# PLD_Local-Supply.net
KiCad netlist of a schematic drawn in Altium Designer
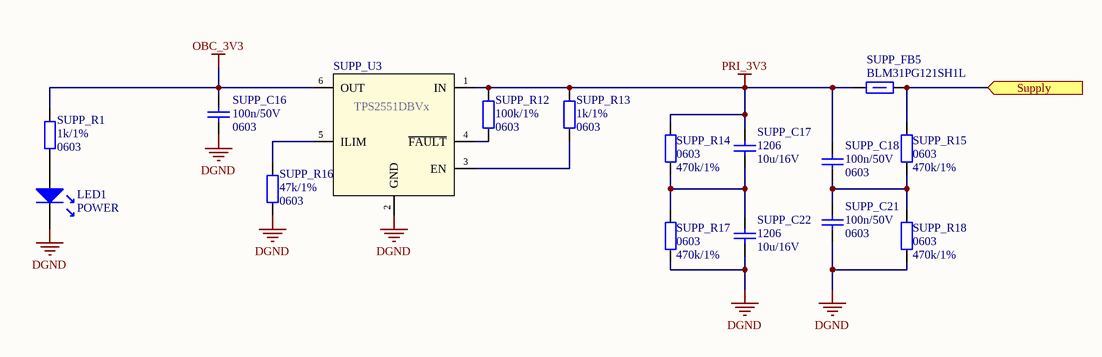
[diagram p0: PLD_Local-Supply.SchDoc]

(export (version "E")
  (design (tool "Eeschema 10.0.6"))
  (components
    (comp (ref "LED1")
      (value "POWER")
      (footprint "SMD_LED_1206")
      (description "LED diode, SMD1206 package.")
      (libsource (lib "diodes") (part "LED-1206_RED"))
    )
    (comp (ref "SUPP_C16")
      (value "100n/50V")
      (footprint "SMD_Capacitor_0603")
      (description "Ceramic Cap Kemet COTS 100n/50V X7R 0603")
      (fields
        (field (name "MANUFACTURER") "Kemet")
        (field (name "MANUFACTURERPARTNUMBER") "C0603T104K5RALTU")
        (field (name "PACKAGE") "0603")
      )
      (libsource (lib "capacitors") (part "Cer_C0603T104K5RALTU"))
    )
    (comp (ref "SUPP_C17")
      (value "10u/16V")
      (footprint "SMD_Capacitor_1206")
      (description "Ceramic Cap Kemet COTS 10u/16V X7R 1206")
      (fields
        (field (name "MANUFACTURERPARTNUMBER") "C1206T106K4RACTU")
        (field (name "MANUFACTURER") "Kemet")
        (field (name "PACKGE") "1206")
      )
      (libsource (lib "capacitors") (part "Cer_C1206T106K4RACTU"))
    )
    (comp (ref "SUPP_C18")
      (value "100n/50V")
      (footprint "SMD_Capacitor_0603")
      (description "Ceramic Cap Kemet COTS 100n/50V X7R 0603")
      (fields
        (field (name "MANUFACTURER") "Kemet")
        (field (name "MANUFACTURERPARTNUMBER") "C0603T104K5RALTU")
        (field (name "PACKAGE") "0603")
      )
      (libsource (lib "capacitors") (part "Cer_C0603T104K5RALTU"))
    )
    (comp (ref "SUPP_C21")
      (value "100n/50V")
      (footprint "SMD_Capacitor_0603")
      (description "Ceramic Cap Kemet COTS 100n/50V X7R 0603")
      (fields
        (field (name "MANUFACTURER") "Kemet")
        (field (name "MANUFACTURERPARTNUMBER") "C0603T104K5RALTU")
        (field (name "PACKAGE") "0603")
      )
      (libsource (lib "capacitors") (part "Cer_C0603T104K5RALTU"))
    )
    (comp (ref "SUPP_C22")
      (value "10u/16V")
      (footprint "SMD_Capacitor_1206")
      (description "Ceramic Cap Kemet COTS 10u/16V X7R 1206")
      (fields
        (field (name "MANUFACTURERPARTNUMBER") "C1206T106K4RACTU")
        (field (name "MANUFACTURER") "Kemet")
        (field (name "PACKGE") "1206")
      )
      (libsource (lib "capacitors") (part "Cer_C1206T106K4RACTU"))
    )
    (comp (ref "SUPP_FB5")
      (value "120R/100MHz")
      (footprint "SMD_FerriteBead_1206")
      (description "Ferrite bead, 1206, 0.02HM, 3.5A.")
      (fields (field (name "MANUFACTURER") "Murata") (field (name "MANUFACTURERPARTNUMBER") "BLM31PG121SH1L"))
      (libsource (lib "inductors") (part "BLM31PG121SH1L"))
    )
    (comp (ref "SUPP_R1")
      (value "1k/1%")
      (footprint "SMD_Resistor_0603")
      (description "1k/1% Vishay CRCW 0603 Resistor. 100mW, 100ppm, 75V.")
      (fields
        (field (name "MANUFACTURER") "Vishay")
        (field (name "MANUFACTURERPARTNUMBER") "CRCW06031K00FKxxxx")
        (field (name "PACKAGE") "0603")
      )
      (libsource (lib "resistors") (part "CRCW06031K00FKxxxx"))
    )
    (comp (ref "SUPP_R12")
      (value "100k/1%")
      (footprint "SMD_Resistor_0603")
      (description "100k/1% Vishay CRCW 0603 Resistor. 100mW, 100ppm, 75V.")
      (fields
        (field (name "MANUFACTURER") "Vishay")
        (field (name "MANUFACTURERPARTNUMBER") "CRCW0603100KFKxxxx")
        (field (name "PACKAGE") "0603")
      )
      (libsource (lib "resistors") (part "CRCW0603100KFKxxxx"))
    )
    (comp (ref "SUPP_R13")
      (value "1k/1%")
      (footprint "SMD_Resistor_0603")
      (description "1k/1% Vishay CRCW 0603 Resistor. 100mW, 100ppm, 75V.")
      (fields
        (field (name "MANUFACTURER") "Vishay")
        (field (name "MANUFACTURERPARTNUMBER") "CRCW06031K00FKxxxx")
        (field (name "PACKAGE") "0603")
      )
      (libsource (lib "resistors") (part "CRCW06031K00FKxxxx"))
    )
    (comp (ref "SUPP_R14")
      (value "470k/1%")
      (footprint "SMD_Resistor_0603")
      (description "470k/1% Vishay CRCW 0603 Resistor. 100mW, 100ppm, 75V.")
      (fields
        (field (name "MANUFACTURER") "Vishay")
        (field (name "MANUFACTURERPARTNUMBER") "CRCW0603470KFKxxxx")
        (field (name "PACKAGE") "0603")
      )
      (libsource (lib "resistors") (part "CRCW0603470KFKxxxx"))
    )
    (comp (ref "SUPP_R15")
      (value "470k/1%")
      (footprint "SMD_Resistor_0603")
      (description "470k/1% Vishay CRCW 0603 Resistor. 100mW, 100ppm, 75V.")
      (fields
        (field (name "MANUFACTURER") "Vishay")
        (field (name "MANUFACTURERPARTNUMBER") "CRCW0603470KFKxxxx")
        (field (name "PACKAGE") "0603")
      )
      (libsource (lib "") (part "CRCW0603470KFKxxxx_1"))
    )
    (comp (ref "SUPP_R16")
      (value "47k/1%")
      (footprint "SMD_Resistor_0603")
      (description "47k/1% Vishay CRCW 0603 Resistor. 100mW, 100ppm, 75V.")
      (fields
        (field (name "MANUFACTURER") "Vishay")
        (field (name "MANUFACTURERPARTNUMBER") "CRCW060347K0FKxxxx")
        (field (name "PACKAGE") "0603")
      )
      (libsource (lib "resistors") (part "CRCW060347K0FKxxxx"))
    )
    (comp (ref "SUPP_R17")
      (value "470k/1%")
      (footprint "SMD_Resistor_0603")
      (description "470k/1% Vishay CRCW 0603 Resistor. 100mW, 100ppm, 75V.")
      (fields
        (field (name "MANUFACTURER") "Vishay")
        (field (name "MANUFACTURERPARTNUMBER") "CRCW0603470KFKxxxx")
        (field (name "PACKAGE") "0603")
      )
      (libsource (lib "resistors") (part "CRCW0603470KFKxxxx"))
    )
    (comp (ref "SUPP_R18")
      (value "470k/1%")
      (footprint "SMD_Resistor_0603")
      (description "470k/1% Vishay CRCW 0603 Resistor. 100mW, 100ppm, 75V.")
      (fields
        (field (name "MANUFACTURER") "Vishay")
        (field (name "MANUFACTURERPARTNUMBER") "CRCW0603470KFKxxxx")
        (field (name "PACKAGE") "0603")
      )
      (libsource (lib "") (part "CRCW0603470KFKxxxx_1"))
    )
    (comp (ref "SUPP_U3")
      (value "TPS2551DBVx")
      (footprint "SOT23-6")
      (description "Adjustable Current-Limited Power-Distribution Switch.")
      (fields (field (name "MANUFACTURER") "Texas Instruments"))
      (libsource (lib "microcircuits") (part "TPS2551DBVx"))
    )
  )
  (nets
    (net (code "1") (name "/Supply") (class "Default")
      (node (ref "SUPP_FB5") (pin "1") (pinfunction "1_1") (pintype "passive"))
      (node (ref "SUPP_R15") (pin "1") (pinfunction "1_1") (pintype "passive"))
    )
    (net (code "2") (name "DGND") (class "Default")
      (node (ref "LED1") (pin "K") (pinfunction "K_K") (pintype "passive"))
      (node (ref "SUPP_C16") (pin "1") (pinfunction "1_1") (pintype "passive"))
      (node (ref "SUPP_C21") (pin "2") (pinfunction "2_2") (pintype "passive"))
      (node (ref "SUPP_C22") (pin "2") (pinfunction "2_2") (pintype "passive"))
      (node (ref "SUPP_R16") (pin "2") (pinfunction "2_2") (pintype "passive"))
      (node (ref "SUPP_R17") (pin "2") (pinfunction "2_2") (pintype "passive"))
      (node (ref "SUPP_R18") (pin "2") (pinfunction "2_2") (pintype "passive"))
      (node (ref "SUPP_U3") (pin "2") (pinfunction "GND_2") (pintype "passive"))
    )
    (net (code "3") (name "Net-(LED1-PadA)") (class "Default")
      (node (ref "LED1") (pin "A") (pinfunction "A_A") (pintype "passive"))
      (node (ref "SUPP_R1") (pin "2") (pinfunction "2_2") (pintype "passive"))
    )
    (net (code "4") (name "Net-(SUPP_C17-Pad2)") (class "Default")
      (node (ref "SUPP_C17") (pin "2") (pinfunction "2_2") (pintype "passive"))
      (node (ref "SUPP_C22") (pin "1") (pinfunction "1_1") (pintype "passive"))
      (node (ref "SUPP_R14") (pin "2") (pinfunction "2_2") (pintype "passive"))
      (node (ref "SUPP_R17") (pin "1") (pinfunction "1_1") (pintype "passive"))
    )
    (net (code "5") (name "Net-(SUPP_C18-Pad2)") (class "Default")
      (node (ref "SUPP_C18") (pin "2") (pinfunction "2_2") (pintype "passive"))
      (node (ref "SUPP_C21") (pin "1") (pinfunction "1_1") (pintype "passive"))
      (node (ref "SUPP_R15") (pin "2") (pinfunction "2_2") (pintype "passive"))
      (node (ref "SUPP_R18") (pin "1") (pinfunction "1_1") (pintype "passive"))
    )
    (net (code "6") (name "Net-(SUPP_U3-EN)") (class "Default")
      (node (ref "SUPP_R13") (pin "2") (pinfunction "2_2") (pintype "passive"))
      (node (ref "SUPP_U3") (pin "3") (pinfunction "EN_3") (pintype "passive"))
    )
    (net (code "7") (name "Net-(SUPP_U3-ILIM)") (class "Default")
      (node (ref "SUPP_R16") (pin "1") (pinfunction "1_1") (pintype "passive"))
      (node (ref "SUPP_U3") (pin "5") (pinfunction "ILIM_5") (pintype "passive"))
    )
    (net (code "8") (name "Net-(SUPP_U3-~{FAULT})") (class "Default")
      (node (ref "SUPP_R12") (pin "2") (pinfunction "2_2") (pintype "passive"))
      (node (ref "SUPP_U3") (pin "4") (pinfunction "~{FAULT}_4") (pintype "passive"))
    )
    (net (code "9") (name "OBC_3V3") (class "Default")
      (node (ref "SUPP_C16") (pin "2") (pinfunction "2_2") (pintype "passive"))
      (node (ref "SUPP_R1") (pin "1") (pinfunction "1_1") (pintype "passive"))
      (node (ref "SUPP_U3") (pin "6") (pinfunction "OUT_6") (pintype "passive"))
    )
    (net (code "10") (name "PRI_3V3") (class "Default")
      (node (ref "SUPP_C17") (pin "1") (pinfunction "1_1") (pintype "passive"))
      (node (ref "SUPP_C18") (pin "1") (pinfunction "1_1") (pintype "passive"))
      (node (ref "SUPP_FB5") (pin "2") (pinfunction "2_2") (pintype "passive"))
      (node (ref "SUPP_R12") (pin "1") (pinfunction "1_1") (pintype "passive"))
      (node (ref "SUPP_R13") (pin "1") (pinfunction "1_1") (pintype "passive"))
      (node (ref "SUPP_R14") (pin "1") (pinfunction "1_1") (pintype "passive"))
      (node (ref "SUPP_U3") (pin "1") (pinfunction "IN_1") (pintype "passive"))
    )
  )
)
